# NS7_Regulator.net
KiCad netlist of a schematic drawn in Altium Designer
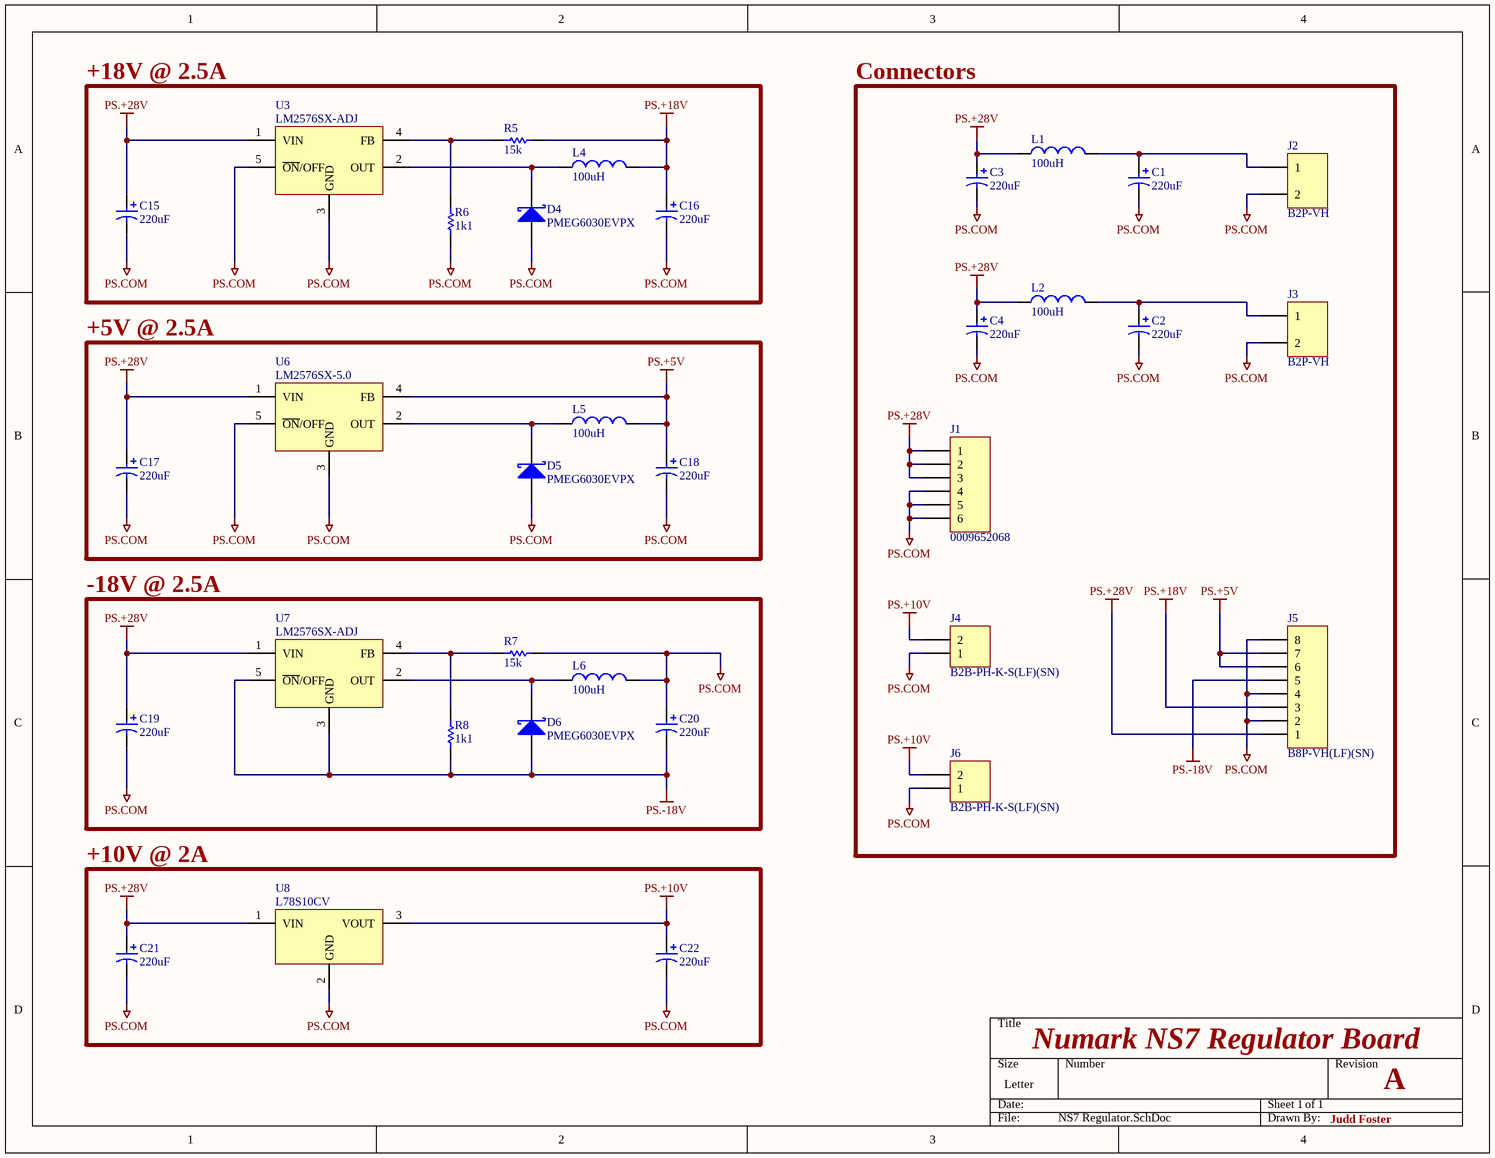
[diagram p0: NS7 Regulator.SchDoc]

(export (version "E")
  (design (tool "Eeschema 10.0.6"))
  (components
    (comp (ref "C1")
      (value "220uF")
      (footprint "Cap,Alum,Thru,D10,H17.5")
      (description "220 µF 50 V Aluminum Electrolytic Capacitors Radial, Can 5000 Hrs @ 105°C")
      (fields
        (field (name "VENDOR PART NUMBER") "1189-3771-1-ND")
        (field (name "MANUFACTURER") "Rubycon")
        (field (name "CREATEDBY") "Judd Foster")
      )
      (libsource (lib "symbols") (part "CAP,Alum,220uF,50VDC,Radial,Thru"))
    )
    (comp (ref "C2")
      (value "220uF")
      (footprint "Cap,Alum,Thru,D10,H17.5")
      (description "220 µF 50 V Aluminum Electrolytic Capacitors Radial, Can 5000 Hrs @ 105°C")
      (fields
        (field (name "VENDOR PART NUMBER") "1189-3771-1-ND")
        (field (name "MANUFACTURER") "Rubycon")
        (field (name "CREATEDBY") "Judd Foster")
      )
      (libsource (lib "symbols") (part "CAP,Alum,220uF,50VDC,Radial,Thru"))
    )
    (comp (ref "C3")
      (value "220uF")
      (footprint "Cap,Alum,Thru,D10,H17.5")
      (description "220 µF 50 V Aluminum Electrolytic Capacitors Radial, Can 5000 Hrs @ 105°C")
      (fields
        (field (name "VENDOR PART NUMBER") "1189-3771-1-ND")
        (field (name "MANUFACTURER") "Rubycon")
        (field (name "CREATEDBY") "Judd Foster")
      )
      (libsource (lib "symbols") (part "CAP,Alum,220uF,50VDC,Radial,Thru"))
    )
    (comp (ref "C4")
      (value "220uF")
      (footprint "Cap,Alum,Thru,D10,H17.5")
      (description "220 µF 50 V Aluminum Electrolytic Capacitors Radial, Can 5000 Hrs @ 105°C")
      (fields
        (field (name "VENDOR PART NUMBER") "1189-3771-1-ND")
        (field (name "MANUFACTURER") "Rubycon")
        (field (name "CREATEDBY") "Judd Foster")
      )
      (libsource (lib "symbols") (part "CAP,Alum,220uF,50VDC,Radial,Thru"))
    )
    (comp (ref "C15")
      (value "220uF")
      (footprint "Cap,Alum,Thru,D10,H17.5")
      (description "220 µF 50 V Aluminum Electrolytic Capacitors Radial, Can 5000 Hrs @ 105°C")
      (fields
        (field (name "VENDOR PART NUMBER") "1189-3771-1-ND")
        (field (name "MANUFACTURER") "Rubycon")
        (field (name "CREATEDBY") "Judd Foster")
      )
      (libsource (lib "symbols") (part "CAP,Alum,220uF,50VDC,Radial,Thru"))
    )
    (comp (ref "C16")
      (value "220uF")
      (footprint "Cap,Alum,Thru,D10,H17.5")
      (description "220 µF 50 V Aluminum Electrolytic Capacitors Radial, Can 5000 Hrs @ 105°C")
      (fields
        (field (name "VENDOR PART NUMBER") "1189-3771-1-ND")
        (field (name "MANUFACTURER") "Rubycon")
        (field (name "CREATEDBY") "Judd Foster")
      )
      (libsource (lib "symbols") (part "CAP,Alum,220uF,50VDC,Radial,Thru"))
    )
    (comp (ref "C17")
      (value "220uF")
      (footprint "Cap,Alum,Thru,D10,H17.5")
      (description "220 µF 50 V Aluminum Electrolytic Capacitors Radial, Can 5000 Hrs @ 105°C")
      (fields
        (field (name "VENDOR PART NUMBER") "1189-3771-1-ND")
        (field (name "MANUFACTURER") "Rubycon")
        (field (name "CREATEDBY") "Judd Foster")
      )
      (libsource (lib "symbols") (part "CAP,Alum,220uF,50VDC,Radial,Thru"))
    )
    (comp (ref "C18")
      (value "220uF")
      (footprint "Cap,Alum,Thru,D10,H17.5")
      (description "220 µF 50 V Aluminum Electrolytic Capacitors Radial, Can 5000 Hrs @ 105°C")
      (fields
        (field (name "VENDOR PART NUMBER") "1189-3771-1-ND")
        (field (name "MANUFACTURER") "Rubycon")
        (field (name "CREATEDBY") "Judd Foster")
      )
      (libsource (lib "symbols") (part "CAP,Alum,220uF,50VDC,Radial,Thru"))
    )
    (comp (ref "C19")
      (value "220uF")
      (footprint "Cap,Alum,Thru,D10,H17.5")
      (description "220 µF 50 V Aluminum Electrolytic Capacitors Radial, Can 5000 Hrs @ 105°C")
      (fields
        (field (name "VENDOR PART NUMBER") "1189-3771-1-ND")
        (field (name "MANUFACTURER") "Rubycon")
        (field (name "CREATEDBY") "Judd Foster")
      )
      (libsource (lib "symbols") (part "CAP,Alum,220uF,50VDC,Radial,Thru"))
    )
    (comp (ref "C20")
      (value "220uF")
      (footprint "Cap,Alum,Thru,D10,H17.5")
      (description "220 µF 50 V Aluminum Electrolytic Capacitors Radial, Can 5000 Hrs @ 105°C")
      (fields
        (field (name "VENDOR PART NUMBER") "1189-3771-1-ND")
        (field (name "MANUFACTURER") "Rubycon")
        (field (name "CREATEDBY") "Judd Foster")
      )
      (libsource (lib "symbols") (part "CAP,Alum,220uF,50VDC,Radial,Thru"))
    )
    (comp (ref "C21")
      (value "220uF")
      (footprint "Cap,Alum,Thru,D10,H17.5")
      (description "220 µF 50 V Aluminum Electrolytic Capacitors Radial, Can 5000 Hrs @ 105°C")
      (fields
        (field (name "VENDOR PART NUMBER") "1189-3771-1-ND")
        (field (name "MANUFACTURER") "Rubycon")
        (field (name "CREATEDBY") "Judd Foster")
      )
      (libsource (lib "symbols") (part "CAP,Alum,220uF,50VDC,Radial,Thru"))
    )
    (comp (ref "C22")
      (value "220uF")
      (footprint "Cap,Alum,Thru,D10,H17.5")
      (description "220 µF 50 V Aluminum Electrolytic Capacitors Radial, Can 5000 Hrs @ 105°C")
      (fields
        (field (name "VENDOR PART NUMBER") "1189-3771-1-ND")
        (field (name "MANUFACTURER") "Rubycon")
        (field (name "CREATEDBY") "Judd Foster")
      )
      (libsource (lib "symbols") (part "CAP,Alum,220uF,50VDC,Radial,Thru"))
    )
    (comp (ref "D4")
      (value "PMEG6030EVPX")
      (footprint "SOD128")
      (description "DIODE SCHOTTKY 60V 3A SOD128")
      (fields
        (field (name "MANUFACTURER") "Nexperia USA Inc.")
        (field (name "VENDOR PART NUMBER") "1727-1349-1-ND")
        (field (name "CREATEDBY") "Judd Foster")
      )
      (libsource (lib "symbols") (part "DIODE,Schottky,60V,3A,SMD"))
    )
    (comp (ref "D5")
      (value "PMEG6030EVPX")
      (footprint "SOD128")
      (description "DIODE SCHOTTKY 60V 3A SOD128")
      (fields
        (field (name "MANUFACTURER") "Nexperia USA Inc.")
        (field (name "VENDOR PART NUMBER") "1727-1349-1-ND")
        (field (name "CREATEDBY") "Judd Foster")
      )
      (libsource (lib "symbols") (part "DIODE,Schottky,60V,3A,SMD"))
    )
    (comp (ref "D6")
      (value "PMEG6030EVPX")
      (footprint "SOD128")
      (description "DIODE SCHOTTKY 60V 3A SOD128")
      (fields
        (field (name "MANUFACTURER") "Nexperia USA Inc.")
        (field (name "VENDOR PART NUMBER") "1727-1349-1-ND")
        (field (name "CREATEDBY") "Judd Foster")
      )
      (libsource (lib "symbols") (part "DIODE,Schottky,60V,3A,SMD"))
    )
    (comp (ref "J1")
      (value "0009652068")
      (footprint "MOLEX_0009652068")
      (description "Connector Header Through Hole 6 position 0.156\" (3.96mm)")
      (fields
        (field (name "MANUFACTURER") "Molex")
        (field (name "VENDOR PART NUMBER") "WM18827-ND")
        (field (name "CREATEDBY") "Judd Foster")
      )
      (libsource (lib "AltiumCmpLib") (part "Conn,Header,Molex,KK,6Pin,3.96mm,Thru"))
    )
    (comp (ref "J2")
      (value "B2P-VH")
      (footprint "JST_B2P-VH")
      (description "1x2P VH 1 3.96mm 2 Brass Plugin,P=3.96mm Wire To Board / Wire To Wire Connector ROHS")
      (fields
        (field (name "MANUFACTURER") "JST Sales America")
        (field (name "VENDOR PART NUMBER") "C160315")
        (field (name "CREATEDBY") "Judd Foster")
      )
      (libsource (lib "AltiumCmpLib") (part "Conn,Header,JST,VH,2Pin,3.96mm,Thru"))
    )
    (comp (ref "J3")
      (value "B2P-VH")
      (footprint "JST_B2P-VH")
      (description "1x2P VH 1 3.96mm 2 Brass Plugin,P=3.96mm Wire To Board / Wire To Wire Connector ROHS")
      (fields
        (field (name "MANUFACTURER") "JST Sales America")
        (field (name "VENDOR PART NUMBER") "C160315")
        (field (name "CREATEDBY") "Judd Foster")
      )
      (libsource (lib "AltiumCmpLib") (part "Conn,Header,JST,VH,2Pin,3.96mm,Thru"))
    )
    (comp (ref "J4")
      (value "B2B-PH-K-S(LF)(SN)")
      (footprint "JST_B2B-PH-K-S")
      (description "1x2P PH 1 2mm 2 Brass Plugin,P=2mm Wire To Board / Wire To Wire Connector ROHS")
      (fields
        (field (name "MANUFACTURER") "JST Sales America")
        (field (name "MANUFACTURER PART NUMBER") "B2B-PH-K-S")
        (field (name "CREATEDBY") "Judd Foster")
      )
      (libsource (lib "AltiumCmpLib") (part "Conn,Header,JST,PH,2Pin,2mm,Thru"))
    )
    (comp (ref "J5")
      (value "B8P-VH(LF)(SN)")
      (footprint "JST_B8P-VH")
      (description "1x8P VH 1 3.96mm 8 Brass Plugin,P=3.96mm Wire To Board / Wire To Wire Connector ROHS")
      (fields
        (field (name "MANUFACTURER") "JST Sales America")
        (field (name "MANUFACTURER PART NUMBER") "B8P-VH")
        (field (name "CREATEDBY") "Judd Foster")
      )
      (libsource (lib "AltiumCmpLib") (part "Conn,Header,JST,VH,8Pin,3.96mm,Thru"))
    )
    (comp (ref "J6")
      (value "B2B-PH-K-S(LF)(SN)")
      (footprint "JST_B2B-PH-K-S")
      (description "1x2P PH 1 2mm 2 Brass Plugin,P=2mm Wire To Board / Wire To Wire Connector ROHS")
      (fields
        (field (name "MANUFACTURER") "JST Sales America")
        (field (name "MANUFACTURER PART NUMBER") "B2B-PH-K-S")
        (field (name "CREATEDBY") "Judd Foster")
      )
      (libsource (lib "AltiumCmpLib") (part "Conn,Header,JST,PH,2Pin,2mm,Thru"))
    )
    (comp (ref "L1")
      (value "100uH")
      (footprint "IND,WIREWOUND,12x12,SMD")
      (description "FIXED IND 100UH 2.5A 110 MOHM")
      (fields
        (field (name "VENDOR PART NUMBER") "732-1248-1-ND")
        (field (name "MANUFACTURER") "Würth Elektronik")
        (field (name "CREATEDBY") "Judd Foster")
      )
      (libsource (lib "symbols") (part "IND,100uH,2.5A,Wirewound,SMD"))
    )
    (comp (ref "L2")
      (value "100uH")
      (footprint "IND,WIREWOUND,12x12,SMD")
      (description "FIXED IND 100UH 2.5A 110 MOHM")
      (fields
        (field (name "VENDOR PART NUMBER") "732-1248-1-ND")
        (field (name "MANUFACTURER") "Würth Elektronik")
        (field (name "CREATEDBY") "Judd Foster")
      )
      (libsource (lib "symbols") (part "IND,100uH,2.5A,Wirewound,SMD"))
    )
    (comp (ref "L4")
      (value "100uH")
      (footprint "IND,WIREWOUND,12x12,SMD")
      (description "FIXED IND 100UH 2.5A 110 MOHM")
      (fields
        (field (name "VENDOR PART NUMBER") "732-1248-1-ND")
        (field (name "MANUFACTURER") "Würth Elektronik")
        (field (name "CREATEDBY") "Judd Foster")
      )
      (libsource (lib "symbols") (part "IND,100uH,2.5A,Wirewound,SMD"))
    )
    (comp (ref "L5")
      (value "100uH")
      (footprint "IND,WIREWOUND,12x12,SMD")
      (description "FIXED IND 100UH 2.5A 110 MOHM")
      (fields
        (field (name "VENDOR PART NUMBER") "732-1248-1-ND")
        (field (name "MANUFACTURER") "Würth Elektronik")
        (field (name "CREATEDBY") "Judd Foster")
      )
      (libsource (lib "symbols") (part "IND,100uH,2.5A,Wirewound,SMD"))
    )
    (comp (ref "L6")
      (value "100uH")
      (footprint "IND,WIREWOUND,12x12,SMD")
      (description "FIXED IND 100UH 2.5A 110 MOHM")
      (fields
        (field (name "VENDOR PART NUMBER") "732-1248-1-ND")
        (field (name "MANUFACTURER") "Würth Elektronik")
        (field (name "CREATEDBY") "Judd Foster")
      )
      (libsource (lib "symbols") (part "IND,100uH,2.5A,Wirewound,SMD"))
    )
    (comp (ref "R5")
      (value "15k")
      (footprint "RES,0402")
      (description "15 kOhms ±1% 0.063W, 1/16W Chip Resistor 0402 (1005 Metric) Thick Film")
      (fields
        (field (name "MANUFACTURER") "Walsin Technology Corporation")
        (field (name "MANUFACTURER PART NUMBER") "WR04X1502FTL")
        (field (name "CREATEDBY") "Judd Foster")
      )
      (libsource (lib "symbols") (part "RES,15k,1%,0.1W,0402"))
    )
    (comp (ref "R6")
      (value "1k1")
      (footprint "RES,0402")
      (description "1.1 kOhms ±1% 0.063W, 1/16W Chip Resistor 0402 (1005 Metric) Moisture Resistant Thick Film")
      (fields
        (field (name "MANUFACTURER") "Yageo")
        (field (name "MANUFACTURER PART NUMBER") "RC0402FR-071K1L")
        (field (name "CREATEDBY") "Judd Foster")
      )
      (libsource (lib "symbols") (part "RES,1k1,1%,0.063W,0402"))
    )
    (comp (ref "R7")
      (value "15k")
      (footprint "RES,0402")
      (description "15 kOhms ±1% 0.063W, 1/16W Chip Resistor 0402 (1005 Metric) Thick Film")
      (fields
        (field (name "MANUFACTURER") "Walsin Technology Corporation")
        (field (name "MANUFACTURER PART NUMBER") "WR04X1502FTL")
        (field (name "CREATEDBY") "Judd Foster")
      )
      (libsource (lib "symbols") (part "RES,15k,1%,0.1W,0402"))
    )
    (comp (ref "R8")
      (value "1k1")
      (footprint "RES,0402")
      (description "1.1 kOhms ±1% 0.063W, 1/16W Chip Resistor 0402 (1005 Metric) Moisture Resistant Thick Film")
      (fields
        (field (name "MANUFACTURER") "Yageo")
        (field (name "MANUFACTURER PART NUMBER") "RC0402FR-071K1L")
        (field (name "CREATEDBY") "Judd Foster")
      )
      (libsource (lib "symbols") (part "RES,1k1,1%,0.063W,0402"))
    )
    (comp (ref "U3")
      (value "LM2576SX-ADJ")
      (footprint "TO263-5")
      (fields
        (field (name "MANUFACTURER PART NUMBER") "LM2576SX-ADJ/NOPB")
        (field (name "MANUFACTURER") "Texas Instruments")
        (field (name "VENDOR PART NUMBER") "LM2576SX-ADJ/NOPBCT-ND")
        (field (name "CREATEDBY") "Judd Foster")
      )
      (libsource (lib "symbols") (part "LM2576SX-ADJ"))
    )
    (comp (ref "U6")
      (value "LM2576SX-5.0")
      (footprint "TO263-5")
      (fields
        (field (name "MANUFACTURER PART NUMBER") "LM2576SX-5.0/NOPB")
        (field (name "MANUFACTURER") "Texas Instruments")
        (field (name "VENDOR PART NUMBER") "LM2576SX-5.0/NOPBCT-ND")
        (field (name "CREATEDBY") "Judd Foster")
      )
      (libsource (lib "symbols") (part "LM2576SX-5.0"))
    )
    (comp (ref "U7")
      (value "LM2576SX-ADJ")
      (footprint "TO263-5")
      (fields
        (field (name "MANUFACTURER PART NUMBER") "LM2576SX-ADJ/NOPB")
        (field (name "MANUFACTURER") "Texas Instruments")
        (field (name "VENDOR PART NUMBER") "LM2576SX-ADJ/NOPBCT-ND")
        (field (name "CREATEDBY") "Judd Foster")
      )
      (libsource (lib "symbols") (part "LM2576SX-ADJ"))
    )
    (comp (ref "U8")
      (value "L78S10CV")
      (footprint "TO-220,PCB Mount")
      (description "Linear Voltage Regulator IC Positive Fixed 1 Output 2A TO-220")
      (fields
        (field (name "MANUFACTURER") "STMicroelectronics")
        (field (name "VENDOR PART NUMBER") "497-6039-5-ND")
        (field (name "CREATEDBY") "Judd Foster")
      )
      (libsource (lib "symbols") (part "L78S10CV"))
    )
  )
  (nets
    (net (code "1") (name "Net-(C1-Pad1)") (class "Default")
      (node (ref "C1") (pin "1") (pinfunction "1_1") (pintype "passive"))
      (node (ref "J2") (pin "1") (pinfunction "1_1") (pintype "passive"))
      (node (ref "L1") (pin "2") (pinfunction "2_2") (pintype "passive"))
    )
    (net (code "2") (name "Net-(C2-Pad1)") (class "Default")
      (node (ref "C2") (pin "1") (pinfunction "1_1") (pintype "passive"))
      (node (ref "J3") (pin "1") (pinfunction "1_1") (pintype "passive"))
      (node (ref "L2") (pin "2") (pinfunction "2_2") (pintype "passive"))
    )
    (net (code "3") (name "Net-(D4-K)") (class "Default")
      (node (ref "D4") (pin "1") (pinfunction "K_1") (pintype "passive"))
      (node (ref "L4") (pin "1") (pinfunction "1_1") (pintype "passive"))
      (node (ref "U3") (pin "2") (pinfunction "OUT_2") (pintype "passive"))
    )
    (net (code "4") (name "Net-(D5-K)") (class "Default")
      (node (ref "D5") (pin "1") (pinfunction "K_1") (pintype "passive"))
      (node (ref "L5") (pin "1") (pinfunction "1_1") (pintype "passive"))
      (node (ref "U6") (pin "2") (pinfunction "OUT_2") (pintype "passive"))
    )
    (net (code "5") (name "Net-(D6-K)") (class "Default")
      (node (ref "D6") (pin "1") (pinfunction "K_1") (pintype "passive"))
      (node (ref "L6") (pin "1") (pinfunction "1_1") (pintype "passive"))
      (node (ref "U7") (pin "2") (pinfunction "OUT_2") (pintype "passive"))
    )
    (net (code "6") (name "Net-(U3-FB)") (class "Default")
      (node (ref "R5") (pin "1") (pinfunction "1_1") (pintype "passive"))
      (node (ref "R6") (pin "2") (pinfunction "2_2") (pintype "passive"))
      (node (ref "U3") (pin "4") (pinfunction "FB_4") (pintype "passive"))
    )
    (net (code "7") (name "Net-(U7-FB)") (class "Default")
      (node (ref "R7") (pin "1") (pinfunction "1_1") (pintype "passive"))
      (node (ref "R8") (pin "2") (pinfunction "2_2") (pintype "passive"))
      (node (ref "U7") (pin "4") (pinfunction "FB_4") (pintype "passive"))
    )
    (net (code "8") (name "PS.+5V") (class "Default")
      (node (ref "C18") (pin "1") (pinfunction "1_1") (pintype "passive"))
      (node (ref "J5") (pin "6") (pinfunction "6_6") (pintype "passive"))
      (node (ref "J5") (pin "7") (pinfunction "7_7") (pintype "passive"))
      (node (ref "L5") (pin "2") (pinfunction "2_2") (pintype "passive"))
      (node (ref "U6") (pin "4") (pinfunction "FB_4") (pintype "passive"))
    )
    (net (code "9") (name "PS.+10V") (class "Default")
      (node (ref "C22") (pin "1") (pinfunction "1_1") (pintype "passive"))
      (node (ref "J4") (pin "2") (pinfunction "2_2") (pintype "passive"))
      (node (ref "J6") (pin "2") (pinfunction "2_2") (pintype "passive"))
      (node (ref "U8") (pin "3") (pinfunction "VOUT_3") (pintype "passive"))
    )
    (net (code "10") (name "PS.+18V") (class "Default")
      (node (ref "C16") (pin "1") (pinfunction "1_1") (pintype "passive"))
      (node (ref "J5") (pin "3") (pinfunction "3_3") (pintype "passive"))
      (node (ref "L4") (pin "2") (pinfunction "2_2") (pintype "passive"))
      (node (ref "R5") (pin "2") (pinfunction "2_2") (pintype "passive"))
    )
    (net (code "11") (name "PS.+28V") (class "Default")
      (node (ref "C15") (pin "1") (pinfunction "1_1") (pintype "passive"))
      (node (ref "C17") (pin "1") (pinfunction "1_1") (pintype "passive"))
      (node (ref "C19") (pin "1") (pinfunction "1_1") (pintype "passive"))
      (node (ref "C21") (pin "1") (pinfunction "1_1") (pintype "passive"))
      (node (ref "C3") (pin "1") (pinfunction "1_1") (pintype "passive"))
      (node (ref "C4") (pin "1") (pinfunction "1_1") (pintype "passive"))
      (node (ref "J1") (pin "1") (pinfunction "1_1") (pintype "passive"))
      (node (ref "J1") (pin "2") (pinfunction "2_2") (pintype "passive"))
      (node (ref "J1") (pin "3") (pinfunction "3_3") (pintype "passive"))
      (node (ref "J5") (pin "1") (pinfunction "1_1") (pintype "passive"))
      (node (ref "L1") (pin "1") (pinfunction "1_1") (pintype "passive"))
      (node (ref "L2") (pin "1") (pinfunction "1_1") (pintype "passive"))
      (node (ref "U3") (pin "1") (pinfunction "VIN_1") (pintype "passive"))
      (node (ref "U6") (pin "1") (pinfunction "VIN_1") (pintype "passive"))
      (node (ref "U7") (pin "1") (pinfunction "VIN_1") (pintype "passive"))
      (node (ref "U8") (pin "1") (pinfunction "VIN_1") (pintype "passive"))
    )
    (net (code "12") (name "PS.-18V") (class "Default")
      (node (ref "C20") (pin "2") (pinfunction "2_2") (pintype "passive"))
      (node (ref "D6") (pin "2") (pinfunction "A_2") (pintype "passive"))
      (node (ref "J5") (pin "5") (pinfunction "5_5") (pintype "passive"))
      (node (ref "R8") (pin "1") (pinfunction "1_1") (pintype "passive"))
      (node (ref "U7") (pin "3") (pinfunction "GND_3") (pintype "passive"))
      (node (ref "U7") (pin "5") (pinfunction "~{ON}/OFF_5") (pintype "passive"))
    )
    (net (code "13") (name "PS.COM") (class "Default")
      (node (ref "C1") (pin "2") (pinfunction "2_2") (pintype "passive"))
      (node (ref "C15") (pin "2") (pinfunction "2_2") (pintype "passive"))
      (node (ref "C16") (pin "2") (pinfunction "2_2") (pintype "passive"))
      (node (ref "C17") (pin "2") (pinfunction "2_2") (pintype "passive"))
      (node (ref "C18") (pin "2") (pinfunction "2_2") (pintype "passive"))
      (node (ref "C19") (pin "2") (pinfunction "2_2") (pintype "passive"))
      (node (ref "C2") (pin "2") (pinfunction "2_2") (pintype "passive"))
      (node (ref "C20") (pin "1") (pinfunction "1_1") (pintype "passive"))
      (node (ref "C21") (pin "2") (pinfunction "2_2") (pintype "passive"))
      (node (ref "C22") (pin "2") (pinfunction "2_2") (pintype "passive"))
      (node (ref "C3") (pin "2") (pinfunction "2_2") (pintype "passive"))
      (node (ref "C4") (pin "2") (pinfunction "2_2") (pintype "passive"))
      (node (ref "D4") (pin "2") (pinfunction "A_2") (pintype "passive"))
      (node (ref "D5") (pin "2") (pinfunction "A_2") (pintype "passive"))
      (node (ref "J1") (pin "4") (pinfunction "4_4") (pintype "passive"))
      (node (ref "J1") (pin "5") (pinfunction "5_5") (pintype "passive"))
      (node (ref "J1") (pin "6") (pinfunction "6_6") (pintype "passive"))
      (node (ref "J2") (pin "2") (pinfunction "2_2") (pintype "passive"))
      (node (ref "J3") (pin "2") (pinfunction "2_2") (pintype "passive"))
      (node (ref "J4") (pin "1") (pinfunction "1_1") (pintype "passive"))
      (node (ref "J5") (pin "2") (pinfunction "2_2") (pintype "passive"))
      (node (ref "J5") (pin "4") (pinfunction "4_4") (pintype "passive"))
      (node (ref "J5") (pin "8") (pinfunction "8_8") (pintype "passive"))
      (node (ref "J6") (pin "1") (pinfunction "1_1") (pintype "passive"))
      (node (ref "L6") (pin "2") (pinfunction "2_2") (pintype "passive"))
      (node (ref "R6") (pin "1") (pinfunction "1_1") (pintype "passive"))
      (node (ref "R7") (pin "2") (pinfunction "2_2") (pintype "passive"))
      (node (ref "U3") (pin "3") (pinfunction "GND_3") (pintype "passive"))
      (node (ref "U3") (pin "5") (pinfunction "~{ON}/OFF_5") (pintype "passive"))
      (node (ref "U6") (pin "3") (pinfunction "GND_3") (pintype "passive"))
      (node (ref "U6") (pin "5") (pinfunction "~{ON}/OFF_5") (pintype "passive"))
      (node (ref "U8") (pin "2") (pinfunction "GND_2") (pintype "passive"))
    )
  )
)
